# AD7616_BLOCK_A.net
KiCad netlist of a schematic drawn in Altium Designer
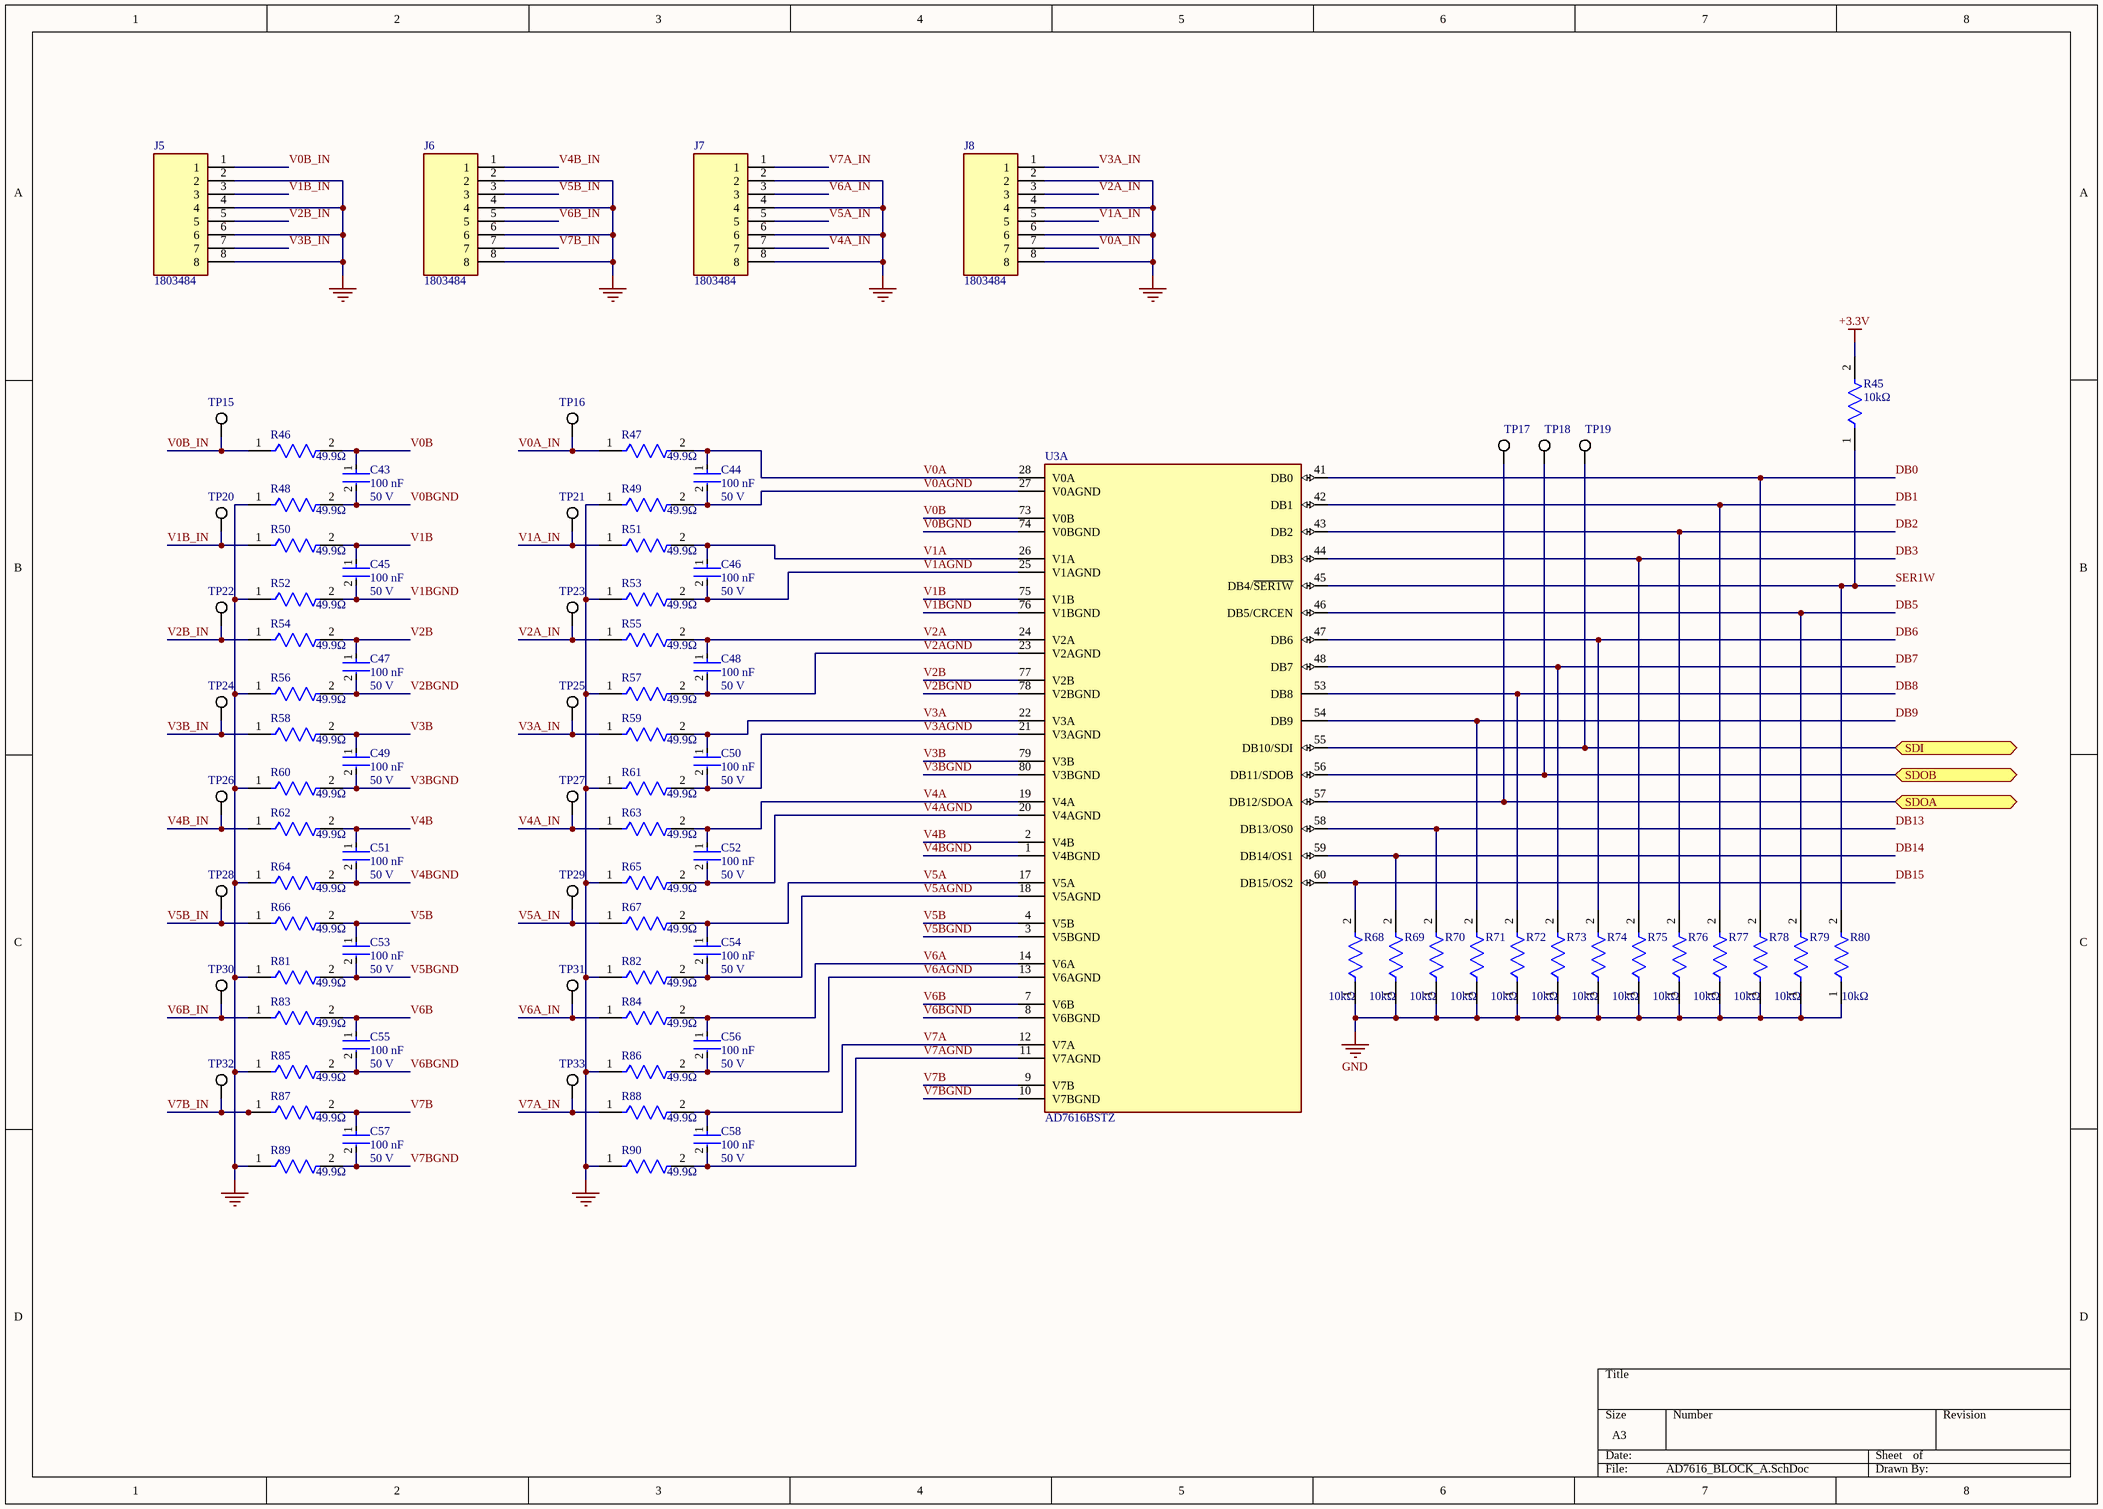
[diagram p0: AD7616_BLOCK_A.SchDoc]

(export (version "E")
  (design (tool "Eeschema 10.0.6"))
  (components
    (comp (ref "C43")
      (value "100 nF")
      (footprint "FP-C0603C-CF-IPC_B")
      (description "CAP CER 0.1UF 50V 20% X7R 0603")
      (fields
        (field (name "VOLTAGE RATING") "50 V")
        (field (name "MANUFACTURER PART NUMBER") "C0603C104M5RACTU")
        (field (name "MANUFACTURER") "KEMET")
      )
      (libsource (lib "Altium Content Vault") (part "b4654b650e69147ec39a6b967a45e02"))
    )
    (comp (ref "C44")
      (value "100 nF")
      (footprint "FP-C0603C-CF-IPC_B")
      (description "CAP CER 0.1UF 50V 20% X7R 0603")
      (fields
        (field (name "VOLTAGE RATING") "50 V")
        (field (name "MANUFACTURER PART NUMBER") "C0603C104M5RACTU")
        (field (name "MANUFACTURER") "KEMET")
      )
      (libsource (lib "Altium Content Vault") (part "b4654b650e69147ec39a6b967a45e02"))
    )
    (comp (ref "C45")
      (value "100 nF")
      (footprint "FP-C0603C-CF-IPC_B")
      (description "CAP CER 0.1UF 50V 20% X7R 0603")
      (fields
        (field (name "VOLTAGE RATING") "50 V")
        (field (name "MANUFACTURER PART NUMBER") "C0603C104M5RACTU")
        (field (name "MANUFACTURER") "KEMET")
      )
      (libsource (lib "Altium Content Vault") (part "b4654b650e69147ec39a6b967a45e02"))
    )
    (comp (ref "C46")
      (value "100 nF")
      (footprint "FP-C0603C-CF-IPC_B")
      (description "CAP CER 0.1UF 50V 20% X7R 0603")
      (fields
        (field (name "VOLTAGE RATING") "50 V")
        (field (name "MANUFACTURER PART NUMBER") "C0603C104M5RACTU")
        (field (name "MANUFACTURER") "KEMET")
      )
      (libsource (lib "Altium Content Vault") (part "b4654b650e69147ec39a6b967a45e02"))
    )
    (comp (ref "C47")
      (value "100 nF")
      (footprint "FP-C0603C-CF-IPC_B")
      (description "CAP CER 0.1UF 50V 20% X7R 0603")
      (fields
        (field (name "VOLTAGE RATING") "50 V")
        (field (name "MANUFACTURER PART NUMBER") "C0603C104M5RACTU")
        (field (name "MANUFACTURER") "KEMET")
      )
      (libsource (lib "Altium Content Vault") (part "b4654b650e69147ec39a6b967a45e02"))
    )
    (comp (ref "C48")
      (value "100 nF")
      (footprint "FP-C0603C-CF-IPC_B")
      (description "CAP CER 0.1UF 50V 20% X7R 0603")
      (fields
        (field (name "VOLTAGE RATING") "50 V")
        (field (name "MANUFACTURER PART NUMBER") "C0603C104M5RACTU")
        (field (name "MANUFACTURER") "KEMET")
      )
      (libsource (lib "Altium Content Vault") (part "b4654b650e69147ec39a6b967a45e02"))
    )
    (comp (ref "C49")
      (value "100 nF")
      (footprint "FP-C0603C-CF-IPC_B")
      (description "CAP CER 0.1UF 50V 20% X7R 0603")
      (fields
        (field (name "VOLTAGE RATING") "50 V")
        (field (name "MANUFACTURER PART NUMBER") "C0603C104M5RACTU")
        (field (name "MANUFACTURER") "KEMET")
      )
      (libsource (lib "Altium Content Vault") (part "b4654b650e69147ec39a6b967a45e02"))
    )
    (comp (ref "C50")
      (value "100 nF")
      (footprint "FP-C0603C-CF-IPC_B")
      (description "CAP CER 0.1UF 50V 20% X7R 0603")
      (fields
        (field (name "VOLTAGE RATING") "50 V")
        (field (name "MANUFACTURER PART NUMBER") "C0603C104M5RACTU")
        (field (name "MANUFACTURER") "KEMET")
      )
      (libsource (lib "Altium Content Vault") (part "b4654b650e69147ec39a6b967a45e02"))
    )
    (comp (ref "C51")
      (value "100 nF")
      (footprint "FP-C0603C-CF-IPC_B")
      (description "CAP CER 0.1UF 50V 20% X7R 0603")
      (fields
        (field (name "VOLTAGE RATING") "50 V")
        (field (name "MANUFACTURER PART NUMBER") "C0603C104M5RACTU")
        (field (name "MANUFACTURER") "KEMET")
      )
      (libsource (lib "Altium Content Vault") (part "b4654b650e69147ec39a6b967a45e02"))
    )
    (comp (ref "C52")
      (value "100 nF")
      (footprint "FP-C0603C-CF-IPC_B")
      (description "CAP CER 0.1UF 50V 20% X7R 0603")
      (fields
        (field (name "VOLTAGE RATING") "50 V")
        (field (name "MANUFACTURER PART NUMBER") "C0603C104M5RACTU")
        (field (name "MANUFACTURER") "KEMET")
      )
      (libsource (lib "Altium Content Vault") (part "b4654b650e69147ec39a6b967a45e02"))
    )
    (comp (ref "C53")
      (value "100 nF")
      (footprint "FP-C0603C-CF-IPC_B")
      (description "CAP CER 0.1UF 50V 20% X7R 0603")
      (fields
        (field (name "VOLTAGE RATING") "50 V")
        (field (name "MANUFACTURER PART NUMBER") "C0603C104M5RACTU")
        (field (name "MANUFACTURER") "KEMET")
      )
      (libsource (lib "Altium Content Vault") (part "b4654b650e69147ec39a6b967a45e02"))
    )
    (comp (ref "C54")
      (value "100 nF")
      (footprint "FP-C0603C-CF-IPC_B")
      (description "CAP CER 0.1UF 50V 20% X7R 0603")
      (fields
        (field (name "VOLTAGE RATING") "50 V")
        (field (name "MANUFACTURER PART NUMBER") "C0603C104M5RACTU")
        (field (name "MANUFACTURER") "KEMET")
      )
      (libsource (lib "Altium Content Vault") (part "b4654b650e69147ec39a6b967a45e02"))
    )
    (comp (ref "C55")
      (value "100 nF")
      (footprint "FP-C0603C-CF-IPC_B")
      (description "CAP CER 0.1UF 50V 20% X7R 0603")
      (fields
        (field (name "VOLTAGE RATING") "50 V")
        (field (name "MANUFACTURER PART NUMBER") "C0603C104M5RACTU")
        (field (name "MANUFACTURER") "KEMET")
      )
      (libsource (lib "Altium Content Vault") (part "b4654b650e69147ec39a6b967a45e02"))
    )
    (comp (ref "C56")
      (value "100 nF")
      (footprint "FP-C0603C-CF-IPC_B")
      (description "CAP CER 0.1UF 50V 20% X7R 0603")
      (fields
        (field (name "VOLTAGE RATING") "50 V")
        (field (name "MANUFACTURER PART NUMBER") "C0603C104M5RACTU")
        (field (name "MANUFACTURER") "KEMET")
      )
      (libsource (lib "Altium Content Vault") (part "b4654b650e69147ec39a6b967a45e02"))
    )
    (comp (ref "C57")
      (value "100 nF")
      (footprint "FP-C0603C-CF-IPC_B")
      (description "CAP CER 0.1UF 50V 20% X7R 0603")
      (fields
        (field (name "VOLTAGE RATING") "50 V")
        (field (name "MANUFACTURER PART NUMBER") "C0603C104M5RACTU")
        (field (name "MANUFACTURER") "KEMET")
      )
      (libsource (lib "Altium Content Vault") (part "b4654b650e69147ec39a6b967a45e02"))
    )
    (comp (ref "C58")
      (value "100 nF")
      (footprint "FP-C0603C-CF-IPC_B")
      (description "CAP CER 0.1UF 50V 20% X7R 0603")
      (fields
        (field (name "VOLTAGE RATING") "50 V")
        (field (name "MANUFACTURER PART NUMBER") "C0603C104M5RACTU")
        (field (name "MANUFACTURER") "KEMET")
      )
      (libsource (lib "Altium Content Vault") (part "b4654b650e69147ec39a6b967a45e02"))
    )
    (comp (ref "J5")
      (value "1803484")
      (footprint "SamacSys:1803484")
      (description "Connector")
      (fields (field (name "MOUSER PART NUMBER") "651-1803484"))
      (libsource (lib "*") (part "1803484"))
    )
    (comp (ref "J6")
      (value "1803484")
      (footprint "SamacSys:1803484")
      (description "Connector")
      (fields (field (name "MOUSER PART NUMBER") "651-1803484"))
      (libsource (lib "*") (part "1803484"))
    )
    (comp (ref "J7")
      (value "1803484")
      (footprint "SamacSys:1803484")
      (description "Connector")
      (fields (field (name "MOUSER PART NUMBER") "651-1803484"))
      (libsource (lib "*") (part "1803484"))
    )
    (comp (ref "J8")
      (value "1803484")
      (footprint "SamacSys:1803484")
      (description "Connector")
      (fields (field (name "MOUSER PART NUMBER") "651-1803484"))
      (libsource (lib "*") (part "1803484"))
    )
    (comp (ref "R45")
      (value "RC0603FR-0710KL")
      (footprint "FP-RC0603-0_55-IPC_B")
      (description "RES 10K OHM 1% 1/10W 0603")
      (fields (field (name "TOLERANCE") "1%") (field (name "RESISTANCE") "10kΩ"))
      (libsource (lib "Altium Content Vault") (part "1029c3af85768c4190bb7ad29bc67b5"))
    )
    (comp (ref "R46")
      (value "AC0603FR-0749R9L")
      (footprint "FP-AC0603-IPC_B")
      (description "RES 49.9Ω 1.00% 0.1W 0603")
      (fields (field (name "RESISTANCE") "49.9Ω") (field (name "TOLERANCE") "1%"))
      (libsource (lib "Altium Content Vault") (part "1029c3af85768c4190bb7ad29bc67b5"))
    )
    (comp (ref "R47")
      (value "AC0603FR-0749R9L")
      (footprint "FP-AC0603-IPC_B")
      (description "RES 49.9Ω 1.00% 0.1W 0603")
      (fields (field (name "RESISTANCE") "49.9Ω") (field (name "TOLERANCE") "1%"))
      (libsource (lib "Altium Content Vault") (part "1029c3af85768c4190bb7ad29bc67b5"))
    )
    (comp (ref "R48")
      (value "AC0603FR-0749R9L")
      (footprint "FP-AC0603-IPC_B")
      (description "RES 49.9Ω 1.00% 0.1W 0603")
      (fields (field (name "RESISTANCE") "49.9Ω") (field (name "TOLERANCE") "1%"))
      (libsource (lib "Altium Content Vault") (part "1029c3af85768c4190bb7ad29bc67b5"))
    )
    (comp (ref "R49")
      (value "AC0603FR-0749R9L")
      (footprint "FP-AC0603-IPC_B")
      (description "RES 49.9Ω 1.00% 0.1W 0603")
      (fields (field (name "RESISTANCE") "49.9Ω") (field (name "TOLERANCE") "1%"))
      (libsource (lib "Altium Content Vault") (part "1029c3af85768c4190bb7ad29bc67b5"))
    )
    (comp (ref "R50")
      (value "AC0603FR-0749R9L")
      (footprint "FP-AC0603-IPC_B")
      (description "RES 49.9Ω 1.00% 0.1W 0603")
      (fields (field (name "RESISTANCE") "49.9Ω") (field (name "TOLERANCE") "1%"))
      (libsource (lib "Altium Content Vault") (part "1029c3af85768c4190bb7ad29bc67b5"))
    )
    (comp (ref "R51")
      (value "AC0603FR-0749R9L")
      (footprint "FP-AC0603-IPC_B")
      (description "RES 49.9Ω 1.00% 0.1W 0603")
      (fields (field (name "RESISTANCE") "49.9Ω") (field (name "TOLERANCE") "1%"))
      (libsource (lib "Altium Content Vault") (part "1029c3af85768c4190bb7ad29bc67b5"))
    )
    (comp (ref "R52")
      (value "AC0603FR-0749R9L")
      (footprint "FP-AC0603-IPC_B")
      (description "RES 49.9Ω 1.00% 0.1W 0603")
      (fields (field (name "RESISTANCE") "49.9Ω") (field (name "TOLERANCE") "1%"))
      (libsource (lib "Altium Content Vault") (part "1029c3af85768c4190bb7ad29bc67b5"))
    )
    (comp (ref "R53")
      (value "AC0603FR-0749R9L")
      (footprint "FP-AC0603-IPC_B")
      (description "RES 49.9Ω 1.00% 0.1W 0603")
      (fields (field (name "RESISTANCE") "49.9Ω") (field (name "TOLERANCE") "1%"))
      (libsource (lib "Altium Content Vault") (part "1029c3af85768c4190bb7ad29bc67b5"))
    )
    (comp (ref "R54")
      (value "AC0603FR-0749R9L")
      (footprint "FP-AC0603-IPC_B")
      (description "RES 49.9Ω 1.00% 0.1W 0603")
      (fields (field (name "RESISTANCE") "49.9Ω") (field (name "TOLERANCE") "1%"))
      (libsource (lib "Altium Content Vault") (part "1029c3af85768c4190bb7ad29bc67b5"))
    )
    (comp (ref "R55")
      (value "AC0603FR-0749R9L")
      (footprint "FP-AC0603-IPC_B")
      (description "RES 49.9Ω 1.00% 0.1W 0603")
      (fields (field (name "RESISTANCE") "49.9Ω") (field (name "TOLERANCE") "1%"))
      (libsource (lib "Altium Content Vault") (part "1029c3af85768c4190bb7ad29bc67b5"))
    )
    (comp (ref "R56")
      (value "AC0603FR-0749R9L")
      (footprint "FP-AC0603-IPC_B")
      (description "RES 49.9Ω 1.00% 0.1W 0603")
      (fields (field (name "RESISTANCE") "49.9Ω") (field (name "TOLERANCE") "1%"))
      (libsource (lib "Altium Content Vault") (part "1029c3af85768c4190bb7ad29bc67b5"))
    )
    (comp (ref "R57")
      (value "AC0603FR-0749R9L")
      (footprint "FP-AC0603-IPC_B")
      (description "RES 49.9Ω 1.00% 0.1W 0603")
      (fields (field (name "RESISTANCE") "49.9Ω") (field (name "TOLERANCE") "1%"))
      (libsource (lib "Altium Content Vault") (part "1029c3af85768c4190bb7ad29bc67b5"))
    )
    (comp (ref "R58")
      (value "AC0603FR-0749R9L")
      (footprint "FP-AC0603-IPC_B")
      (description "RES 49.9Ω 1.00% 0.1W 0603")
      (fields (field (name "RESISTANCE") "49.9Ω") (field (name "TOLERANCE") "1%"))
      (libsource (lib "Altium Content Vault") (part "1029c3af85768c4190bb7ad29bc67b5"))
    )
    (comp (ref "R59")
      (value "AC0603FR-0749R9L")
      (footprint "FP-AC0603-IPC_B")
      (description "RES 49.9Ω 1.00% 0.1W 0603")
      (fields (field (name "RESISTANCE") "49.9Ω") (field (name "TOLERANCE") "1%"))
      (libsource (lib "Altium Content Vault") (part "1029c3af85768c4190bb7ad29bc67b5"))
    )
    (comp (ref "R60")
      (value "AC0603FR-0749R9L")
      (footprint "FP-AC0603-IPC_B")
      (description "RES 49.9Ω 1.00% 0.1W 0603")
      (fields (field (name "RESISTANCE") "49.9Ω") (field (name "TOLERANCE") "1%"))
      (libsource (lib "Altium Content Vault") (part "1029c3af85768c4190bb7ad29bc67b5"))
    )
    (comp (ref "R61")
      (value "AC0603FR-0749R9L")
      (footprint "FP-AC0603-IPC_B")
      (description "RES 49.9Ω 1.00% 0.1W 0603")
      (fields (field (name "RESISTANCE") "49.9Ω") (field (name "TOLERANCE") "1%"))
      (libsource (lib "Altium Content Vault") (part "1029c3af85768c4190bb7ad29bc67b5"))
    )
    (comp (ref "R62")
      (value "AC0603FR-0749R9L")
      (footprint "FP-AC0603-IPC_B")
      (description "RES 49.9Ω 1.00% 0.1W 0603")
      (fields (field (name "RESISTANCE") "49.9Ω") (field (name "TOLERANCE") "1%"))
      (libsource (lib "Altium Content Vault") (part "1029c3af85768c4190bb7ad29bc67b5"))
    )
    (comp (ref "R63")
      (value "AC0603FR-0749R9L")
      (footprint "FP-AC0603-IPC_B")
      (description "RES 49.9Ω 1.00% 0.1W 0603")
      (fields (field (name "RESISTANCE") "49.9Ω") (field (name "TOLERANCE") "1%"))
      (libsource (lib "Altium Content Vault") (part "1029c3af85768c4190bb7ad29bc67b5"))
    )
    (comp (ref "R64")
      (value "AC0603FR-0749R9L")
      (footprint "FP-AC0603-IPC_B")
      (description "RES 49.9Ω 1.00% 0.1W 0603")
      (fields (field (name "RESISTANCE") "49.9Ω") (field (name "TOLERANCE") "1%"))
      (libsource (lib "Altium Content Vault") (part "1029c3af85768c4190bb7ad29bc67b5"))
    )
    (comp (ref "R65")
      (value "AC0603FR-0749R9L")
      (footprint "FP-AC0603-IPC_B")
      (description "RES 49.9Ω 1.00% 0.1W 0603")
      (fields (field (name "RESISTANCE") "49.9Ω") (field (name "TOLERANCE") "1%"))
      (libsource (lib "Altium Content Vault") (part "1029c3af85768c4190bb7ad29bc67b5"))
    )
    (comp (ref "R66")
      (value "AC0603FR-0749R9L")
      (footprint "FP-AC0603-IPC_B")
      (description "RES 49.9Ω 1.00% 0.1W 0603")
      (fields (field (name "RESISTANCE") "49.9Ω") (field (name "TOLERANCE") "1%"))
      (libsource (lib "Altium Content Vault") (part "1029c3af85768c4190bb7ad29bc67b5"))
    )
    (comp (ref "R67")
      (value "AC0603FR-0749R9L")
      (footprint "FP-AC0603-IPC_B")
      (description "RES 49.9Ω 1.00% 0.1W 0603")
      (fields (field (name "RESISTANCE") "49.9Ω") (field (name "TOLERANCE") "1%"))
      (libsource (lib "Altium Content Vault") (part "1029c3af85768c4190bb7ad29bc67b5"))
    )
    (comp (ref "R68")
      (value "RC0603FR-0710KL")
      (footprint "FP-RC0603-0_55-IPC_B")
      (description "RES 10K OHM 1% 1/10W 0603")
      (fields (field (name "TOLERANCE") "1%") (field (name "RESISTANCE") "10kΩ"))
      (libsource (lib "Altium Content Vault") (part "1029c3af85768c4190bb7ad29bc67b5"))
    )
    (comp (ref "R69")
      (value "RC0603FR-0710KL")
      (footprint "FP-RC0603-0_55-IPC_B")
      (description "RES 10K OHM 1% 1/10W 0603")
      (fields (field (name "TOLERANCE") "1%") (field (name "RESISTANCE") "10kΩ"))
      (libsource (lib "Altium Content Vault") (part "1029c3af85768c4190bb7ad29bc67b5"))
    )
    (comp (ref "R70")
      (value "RC0603FR-0710KL")
      (footprint "FP-RC0603-0_55-IPC_B")
      (description "RES 10K OHM 1% 1/10W 0603")
      (fields (field (name "TOLERANCE") "1%") (field (name "RESISTANCE") "10kΩ"))
      (libsource (lib "Altium Content Vault") (part "1029c3af85768c4190bb7ad29bc67b5"))
    )
    (comp (ref "R71")
      (value "RC0603FR-0710KL")
      (footprint "FP-RC0603-0_55-IPC_B")
      (description "RES 10K OHM 1% 1/10W 0603")
      (fields (field (name "TOLERANCE") "1%") (field (name "RESISTANCE") "10kΩ"))
      (libsource (lib "Altium Content Vault") (part "1029c3af85768c4190bb7ad29bc67b5"))
    )
    (comp (ref "R72")
      (value "RC0603FR-0710KL")
      (footprint "FP-RC0603-0_55-IPC_B")
      (description "RES 10K OHM 1% 1/10W 0603")
      (fields (field (name "TOLERANCE") "1%") (field (name "RESISTANCE") "10kΩ"))
      (libsource (lib "Altium Content Vault") (part "1029c3af85768c4190bb7ad29bc67b5"))
    )
    (comp (ref "R73")
      (value "RC0603FR-0710KL")
      (footprint "FP-RC0603-0_55-IPC_B")
      (description "RES 10K OHM 1% 1/10W 0603")
      (fields (field (name "TOLERANCE") "1%") (field (name "RESISTANCE") "10kΩ"))
      (libsource (lib "Altium Content Vault") (part "1029c3af85768c4190bb7ad29bc67b5"))
    )
    (comp (ref "R74")
      (value "RC0603FR-0710KL")
      (footprint "FP-RC0603-0_55-IPC_B")
      (description "RES 10K OHM 1% 1/10W 0603")
      (fields (field (name "TOLERANCE") "1%") (field (name "RESISTANCE") "10kΩ"))
      (libsource (lib "Altium Content Vault") (part "1029c3af85768c4190bb7ad29bc67b5"))
    )
    (comp (ref "R75")
      (value "RC0603FR-0710KL")
      (footprint "FP-RC0603-0_55-IPC_B")
      (description "RES 10K OHM 1% 1/10W 0603")
      (fields (field (name "TOLERANCE") "1%") (field (name "RESISTANCE") "10kΩ"))
      (libsource (lib "Altium Content Vault") (part "1029c3af85768c4190bb7ad29bc67b5"))
    )
    (comp (ref "R76")
      (value "RC0603FR-0710KL")
      (footprint "FP-RC0603-0_55-IPC_B")
      (description "RES 10K OHM 1% 1/10W 0603")
      (fields (field (name "TOLERANCE") "1%") (field (name "RESISTANCE") "10kΩ"))
      (libsource (lib "Altium Content Vault") (part "1029c3af85768c4190bb7ad29bc67b5"))
    )
    (comp (ref "R77")
      (value "RC0603FR-0710KL")
      (footprint "FP-RC0603-0_55-IPC_B")
      (description "RES 10K OHM 1% 1/10W 0603")
      (fields (field (name "TOLERANCE") "1%") (field (name "RESISTANCE") "10kΩ"))
      (libsource (lib "Altium Content Vault") (part "1029c3af85768c4190bb7ad29bc67b5"))
    )
    (comp (ref "R78")
      (value "RC0603FR-0710KL")
      (footprint "FP-RC0603-0_55-IPC_B")
      (description "RES 10K OHM 1% 1/10W 0603")
      (fields (field (name "TOLERANCE") "1%") (field (name "RESISTANCE") "10kΩ"))
      (libsource (lib "Altium Content Vault") (part "1029c3af85768c4190bb7ad29bc67b5"))
    )
    (comp (ref "R79")
      (value "RC0603FR-0710KL")
      (footprint "FP-RC0603-0_55-IPC_B")
      (description "RES 10K OHM 1% 1/10W 0603")
      (fields (field (name "TOLERANCE") "1%") (field (name "RESISTANCE") "10kΩ"))
      (libsource (lib "Altium Content Vault") (part "1029c3af85768c4190bb7ad29bc67b5"))
    )
    (comp (ref "R80")
      (value "RC0603FR-0710KL")
      (footprint "FP-RC0603-0_55-IPC_B")
      (description "RES 10K OHM 1% 1/10W 0603")
      (fields (field (name "TOLERANCE") "1%") (field (name "RESISTANCE") "10kΩ"))
      (libsource (lib "Altium Content Vault") (part "1029c3af85768c4190bb7ad29bc67b5"))
    )
    (comp (ref "R81")
      (value "AC0603FR-0749R9L")
      (footprint "FP-AC0603-IPC_B")
      (description "RES 49.9Ω 1.00% 0.1W 0603")
      (fields (field (name "RESISTANCE") "49.9Ω") (field (name "TOLERANCE") "1%"))
      (libsource (lib "Altium Content Vault") (part "1029c3af85768c4190bb7ad29bc67b5"))
    )
    (comp (ref "R82")
      (value "AC0603FR-0749R9L")
      (footprint "FP-AC0603-IPC_B")
      (description "RES 49.9Ω 1.00% 0.1W 0603")
      (fields (field (name "RESISTANCE") "49.9Ω") (field (name "TOLERANCE") "1%"))
      (libsource (lib "Altium Content Vault") (part "1029c3af85768c4190bb7ad29bc67b5"))
    )
    (comp (ref "R83")
      (value "AC0603FR-0749R9L")
      (footprint "FP-AC0603-IPC_B")
      (description "RES 49.9Ω 1.00% 0.1W 0603")
      (fields (field (name "RESISTANCE") "49.9Ω") (field (name "TOLERANCE") "1%"))
      (libsource (lib "Altium Content Vault") (part "1029c3af85768c4190bb7ad29bc67b5"))
    )
    (comp (ref "R84")
      (value "AC0603FR-0749R9L")
      (footprint "FP-AC0603-IPC_B")
      (description "RES 49.9Ω 1.00% 0.1W 0603")
      (fields (field (name "RESISTANCE") "49.9Ω") (field (name "TOLERANCE") "1%"))
      (libsource (lib "Altium Content Vault") (part "1029c3af85768c4190bb7ad29bc67b5"))
    )
    (comp (ref "R85")
      (value "AC0603FR-0749R9L")
      (footprint "FP-AC0603-IPC_B")
      (description "RES 49.9Ω 1.00% 0.1W 0603")
      (fields (field (name "RESISTANCE") "49.9Ω") (field (name "TOLERANCE") "1%"))
      (libsource (lib "Altium Content Vault") (part "1029c3af85768c4190bb7ad29bc67b5"))
    )
    (comp (ref "R86")
      (value "AC0603FR-0749R9L")
      (footprint "FP-AC0603-IPC_B")
      (description "RES 49.9Ω 1.00% 0.1W 0603")
      (fields (field (name "RESISTANCE") "49.9Ω") (field (name "TOLERANCE") "1%"))
      (libsource (lib "Altium Content Vault") (part "1029c3af85768c4190bb7ad29bc67b5"))
    )
    (comp (ref "R87")
      (value "AC0603FR-0749R9L")
      (footprint "FP-AC0603-IPC_B")
      (description "RES 49.9Ω 1.00% 0.1W 0603")
      (fields (field (name "RESISTANCE") "49.9Ω") (field (name "TOLERANCE") "1%"))
      (libsource (lib "Altium Content Vault") (part "1029c3af85768c4190bb7ad29bc67b5"))
    )
    (comp (ref "R88")
      (value "AC0603FR-0749R9L")
      (footprint "FP-AC0603-IPC_B")
      (description "RES 49.9Ω 1.00% 0.1W 0603")
      (fields (field (name "RESISTANCE") "49.9Ω") (field (name "TOLERANCE") "1%"))
      (libsource (lib "Altium Content Vault") (part "1029c3af85768c4190bb7ad29bc67b5"))
    )
    (comp (ref "R89")
      (value "AC0603FR-0749R9L")
      (footprint "FP-AC0603-IPC_B")
      (description "RES 49.9Ω 1.00% 0.1W 0603")
      (fields (field (name "RESISTANCE") "49.9Ω") (field (name "TOLERANCE") "1%"))
      (libsource (lib "Altium Content Vault") (part "1029c3af85768c4190bb7ad29bc67b5"))
    )
    (comp (ref "R90")
      (value "AC0603FR-0749R9L")
      (footprint "FP-AC0603-IPC_B")
      (description "RES 49.9Ω 1.00% 0.1W 0603")
      (fields (field (name "RESISTANCE") "49.9Ω") (field (name "TOLERANCE") "1%"))
      (libsource (lib "Altium Content Vault") (part "1029c3af85768c4190bb7ad29bc67b5"))
    )
    (comp (ref "TP15")
      (value "5019")
      (footprint "KSTN-5019_V")
      (description "Test Point, 1 Position SMD, RoHS, Tape and Reel")
      (libsource (lib "Altium Content Vault") (part "TESTPOINT_WHITE"))
    )
    (comp (ref "TP16")
      (value "5019")
      (footprint "KSTN-5019_V")
      (description "Test Point, 1 Position SMD, RoHS, Tape and Reel")
      (libsource (lib "Altium Content Vault") (part "TESTPOINT_WHITE"))
    )
    (comp (ref "TP17")
      (value "5019")
      (footprint "KSTN-5019_V")
      (description "Test Point, 1 Position SMD, RoHS, Tape and Reel")
      (libsource (lib "Altium Content Vault") (part "TESTPOINT_WHITE"))
    )
    (comp (ref "TP18")
      (value "5019")
      (footprint "KSTN-5019_V")
      (description "Test Point, 1 Position SMD, RoHS, Tape and Reel")
      (libsource (lib "Altium Content Vault") (part "TESTPOINT_WHITE"))
    )
    (comp (ref "TP19")
      (value "5019")
      (footprint "KSTN-5019_V")
      (description "Test Point, 1 Position SMD, RoHS, Tape and Reel")
      (libsource (lib "Altium Content Vault") (part "TESTPOINT_WHITE"))
    )
    (comp (ref "TP20")
      (value "5019")
      (footprint "KSTN-5019_V")
      (description "Test Point, 1 Position SMD, RoHS, Tape and Reel")
      (libsource (lib "Altium Content Vault") (part "TESTPOINT_WHITE"))
    )
    (comp (ref "TP21")
      (value "5019")
      (footprint "KSTN-5019_V")
      (description "Test Point, 1 Position SMD, RoHS, Tape and Reel")
      (libsource (lib "Altium Content Vault") (part "TESTPOINT_WHITE"))
    )
    (comp (ref "TP22")
      (value "5019")
      (footprint "KSTN-5019_V")
      (description "Test Point, 1 Position SMD, RoHS, Tape and Reel")
      (libsource (lib "Altium Content Vault") (part "TESTPOINT_WHITE"))
    )
    (comp (ref "TP23")
      (value "5019")
      (footprint "KSTN-5019_V")
      (description "Test Point, 1 Position SMD, RoHS, Tape and Reel")
      (libsource (lib "Altium Content Vault") (part "TESTPOINT_WHITE"))
    )
    (comp (ref "TP24")
      (value "5019")
      (footprint "KSTN-5019_V")
      (description "Test Point, 1 Position SMD, RoHS, Tape and Reel")
      (libsource (lib "Altium Content Vault") (part "TESTPOINT_WHITE"))
    )
    (comp (ref "TP25")
      (value "5019")
      (footprint "KSTN-5019_V")
      (description "Test Point, 1 Position SMD, RoHS, Tape and Reel")
      (libsource (lib "Altium Content Vault") (part "TESTPOINT_WHITE"))
    )
    (comp (ref "TP26")
      (value "5019")
      (footprint "KSTN-5019_V")
      (description "Test Point, 1 Position SMD, RoHS, Tape and Reel")
      (libsource (lib "Altium Content Vault") (part "TESTPOINT_WHITE"))
    )
    (comp (ref "TP27")
      (value "5019")
      (footprint "KSTN-5019_V")
      (description "Test Point, 1 Position SMD, RoHS, Tape and Reel")
      (libsource (lib "Altium Content Vault") (part "TESTPOINT_WHITE"))
    )
    (comp (ref "TP28")
      (value "5019")
      (footprint "KSTN-5019_V")
      (description "Test Point, 1 Position SMD, RoHS, Tape and Reel")
      (libsource (lib "Altium Content Vault") (part "TESTPOINT_WHITE"))
    )
    (comp (ref "TP29")
      (value "5019")
      (footprint "KSTN-5019_V")
      (description "Test Point, 1 Position SMD, RoHS, Tape and Reel")
      (libsource (lib "Altium Content Vault") (part "TESTPOINT_WHITE"))
    )
    (comp (ref "TP30")
      (value "5019")
      (footprint "KSTN-5019_V")
      (description "Test Point, 1 Position SMD, RoHS, Tape and Reel")
      (libsource (lib "Altium Content Vault") (part "TESTPOINT_WHITE"))
    )
    (comp (ref "TP31")
      (value "5019")
      (footprint "KSTN-5019_V")
      (description "Test Point, 1 Position SMD, RoHS, Tape and Reel")
      (libsource (lib "Altium Content Vault") (part "TESTPOINT_WHITE"))
    )
    (comp (ref "TP32")
      (value "5019")
      (footprint "KSTN-5019_V")
      (description "Test Point, 1 Position SMD, RoHS, Tape and Reel")
      (libsource (lib "Altium Content Vault") (part "TESTPOINT_WHITE"))
    )
    (comp (ref "TP33")
      (value "5019")
      (footprint "KSTN-5019_V")
      (description "Test Point, 1 Position SMD, RoHS, Tape and Reel")
      (libsource (lib "Altium Content Vault") (part "TESTPOINT_WHITE"))
    )
    (comp (ref "U3")
      (value "AD7616BSTZ")
      (footprint "FP-ST-80-2-IPC_B")
      (description "IC ADC 16BIT SAR 80LQFP")
      (libsource (lib "Altium Content Vault") (part "a44d691853465b646646b7313db8be0"))
    )
  )
  (nets
    (net (code "1") (name "+3.3V") (class "Default")
      (node (ref "R45") (pin "2") (pinfunction "2_2") (pintype "passive"))
    )
    (net (code "2") (name "/DB0") (class "Default")
      (node (ref "R78") (pin "2") (pinfunction "2_2") (pintype "passive"))
      (node (ref "U3") (pin "41") (pinfunction "DB0_41") (pintype "bidirectional"))
    )
    (net (code "3") (name "/DB1") (class "Default")
      (node (ref "R77") (pin "2") (pinfunction "2_2") (pintype "passive"))
      (node (ref "U3") (pin "42") (pinfunction "DB1_42") (pintype "bidirectional"))
    )
    (net (code "4") (name "/DB2") (class "Default")
      (node (ref "R76") (pin "2") (pinfunction "2_2") (pintype "passive"))
      (node (ref "U3") (pin "43") (pinfunction "DB2_43") (pintype "bidirectional"))
    )
    (net (code "5") (name "/DB3") (class "Default")
      (node (ref "R75") (pin "2") (pinfunction "2_2") (pintype "passive"))
      (node (ref "U3") (pin "44") (pinfunction "DB3_44") (pintype "bidirectional"))
    )
    (net (code "6") (name "/DB5") (class "Default")
      (node (ref "R79") (pin "2") (pinfunction "2_2") (pintype "passive"))
      (node (ref "U3") (pin "46") (pinfunction "DB5/CRCEN_46") (pintype "bidirectional"))
    )
    (net (code "7") (name "/DB6") (class "Default")
      (node (ref "R74") (pin "2") (pinfunction "2_2") (pintype "passive"))
      (node (ref "U3") (pin "47") (pinfunction "DB6_47") (pintype "bidirectional"))
    )
    (net (code "8") (name "/DB7") (class "Default")
      (node (ref "R73") (pin "2") (pinfunction "2_2") (pintype "passive"))
      (node (ref "U3") (pin "48") (pinfunction "DB7_48") (pintype "bidirectional"))
    )
    (net (code "9") (name "/DB8") (class "Default")
      (node (ref "R72") (pin "2") (pinfunction "2_2") (pintype "passive"))
      (node (ref "U3") (pin "53") (pinfunction "DB8_53") (pintype "power_in"))
    )
    (net (code "10") (name "/DB9") (class "Default")
      (node (ref "R71") (pin "2") (pinfunction "2_2") (pintype "passive"))
      (node (ref "U3") (pin "54") (pinfunction "DB9_54") (pintype "power_in"))
    )
    (net (code "11") (name "/DB13") (class "Default")
      (node (ref "R70") (pin "2") (pinfunction "2_2") (pintype "passive"))
      (node (ref "U3") (pin "58") (pinfunction "DB13/OS0_58") (pintype "bidirectional"))
    )
    (net (code "12") (name "/DB14") (class "Default")
      (node (ref "R69") (pin "2") (pinfunction "2_2") (pintype "passive"))
      (node (ref "U3") (pin "59") (pinfunction "DB14/OS1_59") (pintype "bidirectional"))
    )
    (net (code "13") (name "/DB15") (class "Default")
      (node (ref "R68") (pin "2") (pinfunction "2_2") (pintype "passive"))
      (node (ref "U3") (pin "60") (pinfunction "DB15/OS2_60") (pintype "bidirectional"))
    )
    (net (code "14") (name "/SDI") (class "Default")
      (node (ref "TP19") (pin "1") (pinfunction "1_1") (pintype "passive"))
      (node (ref "U3") (pin "55") (pinfunction "DB10/SDI_55") (pintype "bidirectional"))
    )
    (net (code "15") (name "/SDOA") (class "Default")
      (node (ref "TP17") (pin "1") (pinfunction "1_1") (pintype "passive"))
      (node (ref "U3") (pin "57") (pinfunction "DB12/SDOA_57") (pintype "bidirectional"))
    )
    (net (code "16") (name "/SDOB") (class "Default")
      (node (ref "TP18") (pin "1") (pinfunction "1_1") (pintype "passive"))
      (node (ref "U3") (pin "56") (pinfunction "DB11/SDOB_56") (pintype "bidirectional"))
    )
    (net (code "17") (name "/SER1W") (class "Default")
      (node (ref "R45") (pin "1") (pinfunction "1_1") (pintype "passive"))
      (node (ref "R80") (pin "2") (pinfunction "2_2") (pintype "passive"))
      (node (ref "U3") (pin "45") (pinfunction "DB4/~{SER1W}_45") (pintype "bidirectional"))
    )
    (net (code "18") (name "/V0A") (class "Default")
      (node (ref "C44") (pin "1") (pinfunction "1_1") (pintype "passive"))
      (node (ref "R47") (pin "2") (pinfunction "2_2") (pintype "passive"))
      (node (ref "U3") (pin "28") (pinfunction "V0A_28") (pintype "power_in"))
    )
    (net (code "19") (name "/V0AGND") (class "Default")
      (node (ref "C44") (pin "2") (pinfunction "2_2") (pintype "passive"))
      (node (ref "R49") (pin "2") (pinfunction "2_2") (pintype "passive"))
      (node (ref "U3") (pin "27") (pinfunction "V0AGND_27") (pintype "power_in"))
    )
    (net (code "20") (name "/V0A_IN") (class "Default")
      (node (ref "J8") (pin "7") (pinfunction "7_7") (pintype "passive"))
      (node (ref "R47") (pin "1") (pinfunction "1_1") (pintype "passive"))
      (node (ref "TP16") (pin "1") (pinfunction "1_1") (pintype "passive"))
    )
    (net (code "21") (name "/V0B") (class "Default")
      (node (ref "C43") (pin "1") (pinfunction "1_1") (pintype "passive"))
      (node (ref "R46") (pin "2") (pinfunction "2_2") (pintype "passive"))
      (node (ref "U3") (pin "73") (pinfunction "V0B_73") (pintype "power_in"))
    )
    (net (code "22") (name "/V0BGND") (class "Default")
      (node (ref "C43") (pin "2") (pinfunction "2_2") (pintype "passive"))
      (node (ref "R48") (pin "2") (pinfunction "2_2") (pintype "passive"))
      (node (ref "U3") (pin "74") (pinfunction "V0BGND_74") (pintype "power_in"))
    )
    (net (code "23") (name "/V0B_IN") (class "Default")
      (node (ref "J5") (pin "1") (pinfunction "1_1") (pintype "passive"))
      (node (ref "R46") (pin "1") (pinfunction "1_1") (pintype "passive"))
      (node (ref "TP15") (pin "1") (pinfunction "1_1") (pintype "passive"))
    )
    (net (code "24") (name "/V1A") (class "Default")
      (node (ref "C46") (pin "1") (pinfunction "1_1") (pintype "passive"))
      (node (ref "R51") (pin "2") (pinfunction "2_2") (pintype "passive"))
      (node (ref "U3") (pin "26") (pinfunction "V1A_26") (pintype "power_in"))
    )
    (net (code "25") (name "/V1AGND") (class "Default")
      (node (ref "C46") (pin "2") (pinfunction "2_2") (pintype "passive"))
      (node (ref "R53") (pin "2") (pinfunction "2_2") (pintype "passive"))
      (node (ref "U3") (pin "25") (pinfunction "V1AGND_25") (pintype "power_in"))
    )
    (net (code "26") (name "/V1A_IN") (class "Default")
      (node (ref "J8") (pin "5") (pinfunction "5_5") (pintype "passive"))
      (node (ref "R51") (pin "1") (pinfunction "1_1") (pintype "passive"))
      (node (ref "TP21") (pin "1") (pinfunction "1_1") (pintype "passive"))
    )
    (net (code "27") (name "/V1B") (class "Default")
      (node (ref "C45") (pin "1") (pinfunction "1_1") (pintype "passive"))
      (node (ref "R50") (pin "2") (pinfunction "2_2") (pintype "passive"))
      (node (ref "U3") (pin "75") (pinfunction "V1B_75") (pintype "power_in"))
    )
    (net (code "28") (name "/V1BGND") (class "Default")
      (node (ref "C45") (pin "2") (pinfunction "2_2") (pintype "passive"))
      (node (ref "R52") (pin "2") (pinfunction "2_2") (pintype "passive"))
      (node (ref "U3") (pin "76") (pinfunction "V1BGND_76") (pintype "power_in"))
    )
    (net (code "29") (name "/V1B_IN") (class "Default")
      (node (ref "J5") (pin "3") (pinfunction "3_3") (pintype "passive"))
      (node (ref "R50") (pin "1") (pinfunction "1_1") (pintype "passive"))
      (node (ref "TP20") (pin "1") (pinfunction "1_1") (pintype "passive"))
    )
    (net (code "30") (name "/V2A") (class "Default")
      (node (ref "C48") (pin "1") (pinfunction "1_1") (pintype "passive"))
      (node (ref "R55") (pin "2") (pinfunction "2_2") (pintype "passive"))
      (node (ref "U3") (pin "24") (pinfunction "V2A_24") (pintype "power_in"))
    )
    (net (code "31") (name "/V2AGND") (class "Default")
      (node (ref "C48") (pin "2") (pinfunction "2_2") (pintype "passive"))
      (node (ref "R57") (pin "2") (pinfunction "2_2") (pintype "passive"))
      (node (ref "U3") (pin "23") (pinfunction "V2AGND_23") (pintype "power_in"))
    )
    (net (code "32") (name "/V2A_IN") (class "Default")
      (node (ref "J8") (pin "3") (pinfunction "3_3") (pintype "passive"))
      (node (ref "R55") (pin "1") (pinfunction "1_1") (pintype "passive"))
      (node (ref "TP23") (pin "1") (pinfunction "1_1") (pintype "passive"))
    )
    (net (code "33") (name "/V2B") (class "Default")
      (node (ref "C47") (pin "1") (pinfunction "1_1") (pintype "passive"))
      (node (ref "R54") (pin "2") (pinfunction "2_2") (pintype "passive"))
      (node (ref "U3") (pin "77") (pinfunction "V2B_77") (pintype "power_in"))
    )
    (net (code "34") (name "/V2BGND") (class "Default")
      (node (ref "C47") (pin "2") (pinfunction "2_2") (pintype "passive"))
      (node (ref "R56") (pin "2") (pinfunction "2_2") (pintype "passive"))
      (node (ref "U3") (pin "78") (pinfunction "V2BGND_78") (pintype "power_in"))
    )
    (net (code "35") (name "/V2B_IN") (class "Default")
      (node (ref "J5") (pin "5") (pinfunction "5_5") (pintype "passive"))
      (node (ref "R54") (pin "1") (pinfunction "1_1") (pintype "passive"))
      (node (ref "TP22") (pin "1") (pinfunction "1_1") (pintype "passive"))
    )
    (net (code "36") (name "/V3A") (class "Default")
      (node (ref "C50") (pin "1") (pinfunction "1_1") (pintype "passive"))
      (node (ref "R59") (pin "2") (pinfunction "2_2") (pintype "passive"))
      (node (ref "U3") (pin "22") (pinfunction "V3A_22") (pintype "power_in"))
    )
    (net (code "37") (name "/V3AGND") (class "Default")
      (node (ref "C50") (pin "2") (pinfunction "2_2") (pintype "passive"))
      (node (ref "R61") (pin "2") (pinfunction "2_2") (pintype "passive"))
      (node (ref "U3") (pin "21") (pinfunction "V3AGND_21") (pintype "power_in"))
    )
    (net (code "38") (name "/V3A_IN") (class "Default")
      (node (ref "J8") (pin "1") (pinfunction "1_1") (pintype "passive"))
      (node (ref "R59") (pin "1") (pinfunction "1_1") (pintype "passive"))
      (node (ref "TP25") (pin "1") (pinfunction "1_1") (pintype "passive"))
    )
    (net (code "39") (name "/V3B") (class "Default")
      (node (ref "C49") (pin "1") (pinfunction "1_1") (pintype "passive"))
      (node (ref "R58") (pin "2") (pinfunction "2_2") (pintype "passive"))
      (node (ref "U3") (pin "79") (pinfunction "V3B_79") (pintype "power_in"))
    )
    (net (code "40") (name "/V3BGND") (class "Default")
      (node (ref "C49") (pin "2") (pinfunction "2_2") (pintype "passive"))
      (node (ref "R60") (pin "2") (pinfunction "2_2") (pintype "passive"))
      (node (ref "U3") (pin "80") (pinfunction "V3BGND_80") (pintype "power_in"))
    )
    (net (code "41") (name "/V3B_IN") (class "Default")
      (node (ref "J5") (pin "7") (pinfunction "7_7") (pintype "passive"))
      (node (ref "R58") (pin "1") (pinfunction "1_1") (pintype "passive"))
      (node (ref "TP24") (pin "1") (pinfunction "1_1") (pintype "passive"))
    )
    (net (code "42") (name "/V4A") (class "Default")
      (node (ref "C52") (pin "1") (pinfunction "1_1") (pintype "passive"))
      (node (ref "R63") (pin "2") (pinfunction "2_2") (pintype "passive"))
      (node (ref "U3") (pin "19") (pinfunction "V4A_19") (pintype "power_in"))
    )
    (net (code "43") (name "/V4AGND") (class "Default")
      (node (ref "C52") (pin "2") (pinfunction "2_2") (pintype "passive"))
      (node (ref "R65") (pin "2") (pinfunction "2_2") (pintype "passive"))
      (node (ref "U3") (pin "20") (pinfunction "V4AGND_20") (pintype "power_in"))
    )
    (net (code "44") (name "/V4A_IN") (class "Default")
      (node (ref "J7") (pin "7") (pinfunction "7_7") (pintype "passive"))
      (node (ref "R63") (pin "1") (pinfunction "1_1") (pintype "passive"))
      (node (ref "TP27") (pin "1") (pinfunction "1_1") (pintype "passive"))
    )
    (net (code "45") (name "/V4B") (class "Default")
      (node (ref "C51") (pin "1") (pinfunction "1_1") (pintype "passive"))
      (node (ref "R62") (pin "2") (pinfunction "2_2") (pintype "passive"))
      (node (ref "U3") (pin "2") (pinfunction "V4B_2") (pintype "power_in"))
    )
    (net (code "46") (name "/V4BGND") (class "Default")
      (node (ref "C51") (pin "2") (pinfunction "2_2") (pintype "passive"))
      (node (ref "R64") (pin "2") (pinfunction "2_2") (pintype "passive"))
      (node (ref "U3") (pin "1") (pinfunction "V4BGND_1") (pintype "power_in"))
    )
    (net (code "47") (name "/V4B_IN") (class "Default")
      (node (ref "J6") (pin "1") (pinfunction "1_1") (pintype "passive"))
      (node (ref "R62") (pin "1") (pinfunction "1_1") (pintype "passive"))
      (node (ref "TP26") (pin "1") (pinfunction "1_1") (pintype "passive"))
    )
    (net (code "48") (name "/V5A") (class "Default")
      (node (ref "C54") (pin "1") (pinfunction "1_1") (pintype "passive"))
      (node (ref "R67") (pin "2") (pinfunction "2_2") (pintype "passive"))
      (node (ref "U3") (pin "17") (pinfunction "V5A_17") (pintype "power_in"))
    )
    (net (code "49") (name "/V5AGND") (class "Default")
      (node (ref "C54") (pin "2") (pinfunction "2_2") (pintype "passive"))
      (node (ref "R82") (pin "2") (pinfunction "2_2") (pintype "passive"))
      (node (ref "U3") (pin "18") (pinfunction "V5AGND_18") (pintype "power_in"))
    )
    (net (code "50") (name "/V5A_IN") (class "Default")
      (node (ref "J7") (pin "5") (pinfunction "5_5") (pintype "passive"))
      (node (ref "R67") (pin "1") (pinfunction "1_1") (pintype "passive"))
      (node (ref "TP29") (pin "1") (pinfunction "1_1") (pintype "passive"))
    )
    (net (code "51") (name "/V5B") (class "Default")
      (node (ref "C53") (pin "1") (pinfunction "1_1") (pintype "passive"))
      (node (ref "R66") (pin "2") (pinfunction "2_2") (pintype "passive"))
      (node (ref "U3") (pin "4") (pinfunction "V5B_4") (pintype "power_in"))
    )
    (net (code "52") (name "/V5BGND") (class "Default")
      (node (ref "C53") (pin "2") (pinfunction "2_2") (pintype "passive"))
      (node (ref "R81") (pin "2") (pinfunction "2_2") (pintype "passive"))
      (node (ref "U3") (pin "3") (pinfunction "V5BGND_3") (pintype "power_in"))
    )
    (net (code "53") (name "/V5B_IN") (class "Default")
      (node (ref "J6") (pin "3") (pinfunction "3_3") (pintype "passive"))
      (node (ref "R66") (pin "1") (pinfunction "1_1") (pintype "passive"))
      (node (ref "TP28") (pin "1") (pinfunction "1_1") (pintype "passive"))
    )
    (net (code "54") (name "/V6A") (class "Default")
      (node (ref "C56") (pin "1") (pinfunction "1_1") (pintype "passive"))
      (node (ref "R84") (pin "2") (pinfunction "2_2") (pintype "passive"))
      (node (ref "U3") (pin "14") (pinfunction "V6A_14") (pintype "power_in"))
    )
    (net (code "55") (name "/V6AGND") (class "Default")
      (node (ref "C56") (pin "2") (pinfunction "2_2") (pintype "passive"))
      (node (ref "R86") (pin "2") (pinfunction "2_2") (pintype "passive"))
      (node (ref "U3") (pin "13") (pinfunction "V6AGND_13") (pintype "power_in"))
    )
    (net (code "56") (name "/V6A_IN") (class "Default")
      (node (ref "J7") (pin "3") (pinfunction "3_3") (pintype "passive"))
      (node (ref "R84") (pin "1") (pinfunction "1_1") (pintype "passive"))
      (node (ref "TP31") (pin "1") (pinfunction "1_1") (pintype "passive"))
    )
    (net (code "57") (name "/V6B") (class "Default")
      (node (ref "C55") (pin "1") (pinfunction "1_1") (pintype "passive"))
      (node (ref "R83") (pin "2") (pinfunction "2_2") (pintype "passive"))
      (node (ref "U3") (pin "7") (pinfunction "V6B_7") (pintype "power_in"))
    )
    (net (code "58") (name "/V6BGND") (class "Default")
      (node (ref "C55") (pin "2") (pinfunction "2_2") (pintype "passive"))
      (node (ref "R85") (pin "2") (pinfunction "2_2") (pintype "passive"))
      (node (ref "U3") (pin "8") (pinfunction "V6BGND_8") (pintype "power_in"))
    )
    (net (code "59") (name "/V6B_IN") (class "Default")
      (node (ref "J6") (pin "5") (pinfunction "5_5") (pintype "passive"))
      (node (ref "R83") (pin "1") (pinfunction "1_1") (pintype "passive"))
      (node (ref "TP30") (pin "1") (pinfunction "1_1") (pintype "passive"))
    )
    (net (code "60") (name "/V7A") (class "Default")
      (node (ref "C58") (pin "1") (pinfunction "1_1") (pintype "passive"))
      (node (ref "R88") (pin "2") (pinfunction "2_2") (pintype "passive"))
      (node (ref "U3") (pin "12") (pinfunction "V7A_12") (pintype "power_in"))
    )
    (net (code "61") (name "/V7AGND") (class "Default")
      (node (ref "C58") (pin "2") (pinfunction "2_2") (pintype "passive"))
      (node (ref "R90") (pin "2") (pinfunction "2_2") (pintype "passive"))
      (node (ref "U3") (pin "11") (pinfunction "V7AGND_11") (pintype "power_in"))
    )
    (net (code "62") (name "/V7A_IN") (class "Default")
      (node (ref "J7") (pin "1") (pinfunction "1_1") (pintype "passive"))
      (node (ref "R88") (pin "1") (pinfunction "1_1") (pintype "passive"))
      (node (ref "TP33") (pin "1") (pinfunction "1_1") (pintype "passive"))
    )
    (net (code "63") (name "/V7B") (class "Default")
      (node (ref "C57") (pin "1") (pinfunction "1_1") (pintype "passive"))
      (node (ref "R87") (pin "2") (pinfunction "2_2") (pintype "passive"))
      (node (ref "U3") (pin "9") (pinfunction "V7B_9") (pintype "power_in"))
    )
    (net (code "64") (name "/V7BGND") (class "Default")
      (node (ref "C57") (pin "2") (pinfunction "2_2") (pintype "passive"))
      (node (ref "R89") (pin "2") (pinfunction "2_2") (pintype "passive"))
      (node (ref "U3") (pin "10") (pinfunction "V7BGND_10") (pintype "power_in"))
    )
    (net (code "65") (name "/V7B_IN") (class "Default")
      (node (ref "J6") (pin "7") (pinfunction "7_7") (pintype "passive"))
      (node (ref "R87") (pin "1") (pinfunction "1_1") (pintype "passive"))
      (node (ref "TP32") (pin "1") (pinfunction "1_1") (pintype "passive"))
    )
    (net (code "66") (name "GND") (class "Default")
      (node (ref "J5") (pin "2") (pinfunction "2_2") (pintype "passive"))
      (node (ref "J5") (pin "4") (pinfunction "4_4") (pintype "passive"))
      (node (ref "J5") (pin "6") (pinfunction "6_6") (pintype "passive"))
      (node (ref "J5") (pin "8") (pinfunction "8_8") (pintype "passive"))
      (node (ref "J6") (pin "2") (pinfunction "2_2") (pintype "passive"))
      (node (ref "J6") (pin "4") (pinfunction "4_4") (pintype "passive"))
      (node (ref "J6") (pin "6") (pinfunction "6_6") (pintype "passive"))
      (node (ref "J6") (pin "8") (pinfunction "8_8") (pintype "passive"))
      (node (ref "J7") (pin "2") (pinfunction "2_2") (pintype "passive"))
      (node (ref "J7") (pin "4") (pinfunction "4_4") (pintype "passive"))
      (node (ref "J7") (pin "6") (pinfunction "6_6") (pintype "passive"))
      (node (ref "J7") (pin "8") (pinfunction "8_8") (pintype "passive"))
      (node (ref "J8") (pin "2") (pinfunction "2_2") (pintype "passive"))
      (node (ref "J8") (pin "4") (pinfunction "4_4") (pintype "passive"))
      (node (ref "J8") (pin "6") (pinfunction "6_6") (pintype "passive"))
      (node (ref "J8") (pin "8") (pinfunction "8_8") (pintype "passive"))
      (node (ref "R48") (pin "1") (pinfunction "1_1") (pintype "passive"))
      (node (ref "R49") (pin "1") (pinfunction "1_1") (pintype "passive"))
      (node (ref "R52") (pin "1") (pinfunction "1_1") (pintype "passive"))
      (node (ref "R53") (pin "1") (pinfunction "1_1") (pintype "passive"))
      (node (ref "R56") (pin "1") (pinfunction "1_1") (pintype "passive"))
      (node (ref "R57") (pin "1") (pinfunction "1_1") (pintype "passive"))
      (node (ref "R60") (pin "1") (pinfunction "1_1") (pintype "passive"))
      (node (ref "R61") (pin "1") (pinfunction "1_1") (pintype "passive"))
      (node (ref "R64") (pin "1") (pinfunction "1_1") (pintype "passive"))
      (node (ref "R65") (pin "1") (pinfunction "1_1") (pintype "passive"))
      (node (ref "R68") (pin "1") (pinfunction "1_1") (pintype "passive"))
      (node (ref "R69") (pin "1") (pinfunction "1_1") (pintype "passive"))
      (node (ref "R70") (pin "1") (pinfunction "1_1") (pintype "passive"))
      (node (ref "R71") (pin "1") (pinfunction "1_1") (pintype "passive"))
      (node (ref "R72") (pin "1") (pinfunction "1_1") (pintype "passive"))
      (node (ref "R73") (pin "1") (pinfunction "1_1") (pintype "passive"))
      (node (ref "R74") (pin "1") (pinfunction "1_1") (pintype "passive"))
      (node (ref "R75") (pin "1") (pinfunction "1_1") (pintype "passive"))
      (node (ref "R76") (pin "1") (pinfunction "1_1") (pintype "passive"))
      (node (ref "R77") (pin "1") (pinfunction "1_1") (pintype "passive"))
      (node (ref "R78") (pin "1") (pinfunction "1_1") (pintype "passive"))
      (node (ref "R79") (pin "1") (pinfunction "1_1") (pintype "passive"))
      (node (ref "R80") (pin "1") (pinfunction "1_1") (pintype "passive"))
      (node (ref "R81") (pin "1") (pinfunction "1_1") (pintype "passive"))
      (node (ref "R82") (pin "1") (pinfunction "1_1") (pintype "passive"))
      (node (ref "R85") (pin "1") (pinfunction "1_1") (pintype "passive"))
      (node (ref "R86") (pin "1") (pinfunction "1_1") (pintype "passive"))
      (node (ref "R89") (pin "1") (pinfunction "1_1") (pintype "passive"))
      (node (ref "R90") (pin "1") (pinfunction "1_1") (pintype "passive"))
    )
  )
)
